# FL-Ver0_6.net
KiCad netlist of a schematic drawn in EAGLE
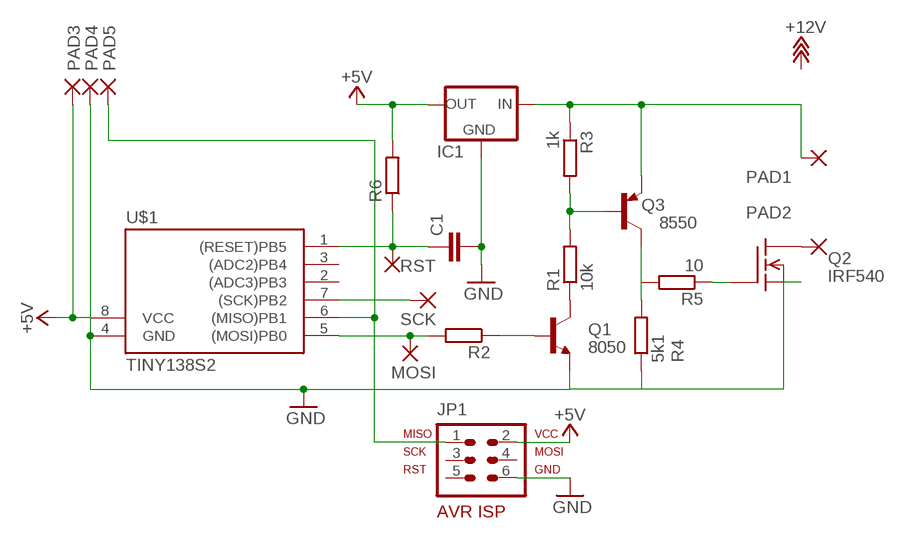
[diagram p0: schematic, sheet 1]

(export (version "E")
  (design (tool "Eeschema 10.0.6"))
  (components
    (comp (ref "C1")
      (value "C-EUC0805")
      (footprint "eagle-import:C0805")
      (libsource (lib "eagle-import") (part "C-EUC0805"))
    )
    (comp (ref "IC1")
      (value "78MXXSDPACK")
      (footprint "eagle-import:DPACK")
      (libsource (lib "eagle-import") (part "78MXXSDPACK"))
    )
    (comp (ref "JP1")
      (value "AVR-ISP-6VERT")
      (footprint "eagle-import:AVR-ISP-6")
      (libsource (lib "eagle-import") (part "AVR-ISP-6VERT"))
    )
    (comp (ref "MOSI")
      (value "1,6/0,8")
      (footprint "eagle-import:1,6_0,8")
      (libsource (lib "eagle-import") (part "1,6/0,8"))
    )
    (comp (ref "PAD1")
      (value "SMD5")
      (footprint "eagle-import:SMD2,54-5,08")
      (libsource (lib "eagle-import") (part "SMD5"))
    )
    (comp (ref "PAD2")
      (value "SMD5")
      (footprint "eagle-import:SMD2,54-5,08")
      (libsource (lib "eagle-import") (part "SMD5"))
    )
    (comp (ref "PAD3")
      (value "SMD5")
      (footprint "eagle-import:SMD2,54-5,08")
      (libsource (lib "eagle-import") (part "SMD5"))
    )
    (comp (ref "PAD4")
      (value "SMD5")
      (footprint "eagle-import:SMD2,54-5,08")
      (libsource (lib "eagle-import") (part "SMD5"))
    )
    (comp (ref "PAD5")
      (value "SMD5")
      (footprint "eagle-import:SMD2,54-5,08")
      (libsource (lib "eagle-import") (part "SMD5"))
    )
    (comp (ref "Q1")
      (value "8050")
      (footprint "eagle-import:TO92-EBC")
      (libsource (lib "eagle-import") (part "-NPN-TO92-EBC"))
    )
    (comp (ref "Q2")
      (value "IRF540")
      (footprint "eagle-import:TO220")
      (libsource (lib "eagle-import") (part "IRF540"))
    )
    (comp (ref "Q3")
      (value "8550")
      (footprint "eagle-import:TO92-EBC")
      (libsource (lib "eagle-import") (part "-PNP-TO92-EBCBC327-16"))
    )
    (comp (ref "R1")
      (value "10k")
      (footprint "eagle-import:0309_12")
      (libsource (lib "eagle-import") (part "R-EU_0309/12"))
    )
    (comp (ref "R2")
      (value "R-EU_0309/12")
      (footprint "eagle-import:0309_12")
      (libsource (lib "eagle-import") (part "R-EU_0309/12"))
    )
    (comp (ref "R3")
      (value "1k")
      (footprint "eagle-import:0309_12")
      (libsource (lib "eagle-import") (part "R-EU_0309/12"))
    )
    (comp (ref "R4")
      (value "5k1")
      (footprint "eagle-import:0309_12")
      (libsource (lib "eagle-import") (part "R-EU_0309/12"))
    )
    (comp (ref "R5")
      (value "10")
      (footprint "eagle-import:0309_12")
      (libsource (lib "eagle-import") (part "R-EU_0309/12"))
    )
    (comp (ref "R6")
      (value "R-EU_M0805")
      (footprint "eagle-import:M0805")
      (libsource (lib "eagle-import") (part "R-EU_M0805"))
    )
    (comp (ref "RST")
      (value "1,6/0,8")
      (footprint "eagle-import:1,6_0,8")
      (libsource (lib "eagle-import") (part "1,6/0,8"))
    )
    (comp (ref "SCK")
      (value "1,6/0,8")
      (footprint "eagle-import:1,6_0,8")
      (libsource (lib "eagle-import") (part "1,6/0,8"))
    )
    (comp (ref "U$1")
      (value "TINY138S2")
      (footprint "eagle-import:SO08")
      (libsource (lib "eagle-import") (part "TINY138S2"))
    )
  )
  (nets
    (net (code "1") (name "+5V") (class "Default")
      (node (ref "IC1") (pin "3") (pinfunction "OUT_3") (pintype "passive"))
      (node (ref "JP1") (pin "2") (pinfunction "2_2") (pintype "passive"))
      (node (ref "PAD3") (pin "1") (pinfunction "P_1") (pintype "passive"))
      (node (ref "R6") (pin "2") (pinfunction "2_2") (pintype "passive"))
      (node (ref "U$1") (pin "8") (pinfunction "VCC_8") (pintype "power_in"))
    )
    (net (code "3") (name "GND") (class "Default")
      (node (ref "C1") (pin "2") (pinfunction "2_2") (pintype "passive"))
      (node (ref "IC1") (pin "2") (pinfunction "GND_2") (pintype "input"))
      (node (ref "JP1") (pin "6") (pinfunction "6_6") (pintype "passive"))
      (node (ref "PAD4") (pin "1") (pinfunction "P_1") (pintype "passive"))
      (node (ref "Q1") (pin "E") (pinfunction "E_E") (pintype "passive"))
      (node (ref "Q2") (pin "3") (pinfunction "S_3") (pintype "passive"))
      (node (ref "R4") (pin "1") (pinfunction "1_1") (pintype "passive"))
      (node (ref "U$1") (pin "4") (pinfunction "GND_4") (pintype "power_in"))
    )
    (net (code "4") (name "Net-(IC1-IN)") (class "Default")
      (node (ref "IC1") (pin "1") (pinfunction "IN_1") (pintype "input"))
      (node (ref "PAD1") (pin "1") (pinfunction "P_1") (pintype "passive"))
      (node (ref "Q3") (pin "E") (pinfunction "E_E") (pintype "passive"))
      (node (ref "R3") (pin "1") (pinfunction "1_1") (pintype "passive"))
    )
    (net (code "5") (name "Net-(MOSI-P)") (class "Default")
      (node (ref "MOSI") (pin "1") (pinfunction "P_1") (pintype "passive"))
      (node (ref "R2") (pin "2") (pinfunction "2_2") (pintype "passive"))
      (node (ref "U$1") (pin "5") (pinfunction "(MOSI)PB0_5") (pintype "bidirectional"))
    )
    (net (code "6") (name "Net-(PAD2-P)") (class "Default")
      (node (ref "PAD2") (pin "1") (pinfunction "P_1") (pintype "passive"))
      (node (ref "Q2") (pin "2") (pinfunction "D_2") (pintype "passive"))
    )
    (net (code "7") (name "Net-(PAD5-P)") (class "Default")
      (node (ref "JP1") (pin "1") (pinfunction "1_1") (pintype "passive"))
      (node (ref "PAD5") (pin "1") (pinfunction "P_1") (pintype "passive"))
      (node (ref "U$1") (pin "6") (pinfunction "(MISO)PB1_6") (pintype "bidirectional"))
    )
    (net (code "8") (name "Net-(Q1-PadB)") (class "Default")
      (node (ref "Q1") (pin "B") (pinfunction "B_B") (pintype "passive"))
      (node (ref "R2") (pin "1") (pinfunction "1_1") (pintype "passive"))
    )
    (net (code "9") (name "Net-(Q1-PadC)") (class "Default")
      (node (ref "Q1") (pin "C") (pinfunction "C_C") (pintype "passive"))
      (node (ref "R1") (pin "1") (pinfunction "1_1") (pintype "passive"))
    )
    (net (code "10") (name "Net-(Q2-G)") (class "Default")
      (node (ref "Q2") (pin "1") (pinfunction "G_1") (pintype "passive"))
      (node (ref "R5") (pin "1") (pinfunction "1_1") (pintype "passive"))
    )
    (net (code "11") (name "Net-(Q3-PadB)") (class "Default")
      (node (ref "Q3") (pin "B") (pinfunction "B_B") (pintype "passive"))
      (node (ref "R1") (pin "2") (pinfunction "2_2") (pintype "passive"))
      (node (ref "R3") (pin "2") (pinfunction "2_2") (pintype "passive"))
    )
    (net (code "12") (name "Net-(Q3-PadC)") (class "Default")
      (node (ref "Q3") (pin "C") (pinfunction "C_C") (pintype "passive"))
      (node (ref "R4") (pin "2") (pinfunction "2_2") (pintype "passive"))
      (node (ref "R5") (pin "2") (pinfunction "2_2") (pintype "passive"))
    )
    (net (code "13") (name "Net-(RST-P)") (class "Default")
      (node (ref "C1") (pin "1") (pinfunction "1_1") (pintype "passive"))
      (node (ref "R6") (pin "1") (pinfunction "1_1") (pintype "passive"))
      (node (ref "RST") (pin "1") (pinfunction "P_1") (pintype "passive"))
      (node (ref "U$1") (pin "1") (pinfunction "(RESET)PB5_1") (pintype "bidirectional"))
    )
    (net (code "14") (name "Net-(SCK-P)") (class "Default")
      (node (ref "SCK") (pin "1") (pinfunction "P_1") (pintype "passive"))
      (node (ref "U$1") (pin "7") (pinfunction "(SCK)PB2_7") (pintype "bidirectional"))
    )
    (net (code "15") (name "unconnected-(JP1-Pad3)") (class "Default")
      (node (ref "JP1") (pin "3") (pinfunction "3_3") (pintype "passive"))
    )
    (net (code "16") (name "unconnected-(JP1-Pad4)") (class "Default")
      (node (ref "JP1") (pin "4") (pinfunction "4_4") (pintype "passive"))
    )
    (net (code "17") (name "unconnected-(JP1-Pad5)") (class "Default")
      (node (ref "JP1") (pin "5") (pinfunction "5_5") (pintype "passive"))
    )
    (net (code "18") (name "unconnected-(U$1-(ADC2)PB4-Pad3)") (class "Default")
      (node (ref "U$1") (pin "3") (pinfunction "(ADC2)PB4_3") (pintype "bidirectional"))
    )
    (net (code "19") (name "unconnected-(U$1-(ADC3)PB3-Pad2)") (class "Default")
      (node (ref "U$1") (pin "2") (pinfunction "(ADC3)PB3_2") (pintype "bidirectional"))
    )
  )
)
